# BuckBoost.net
KiCad netlist of a schematic drawn in Altium Designer
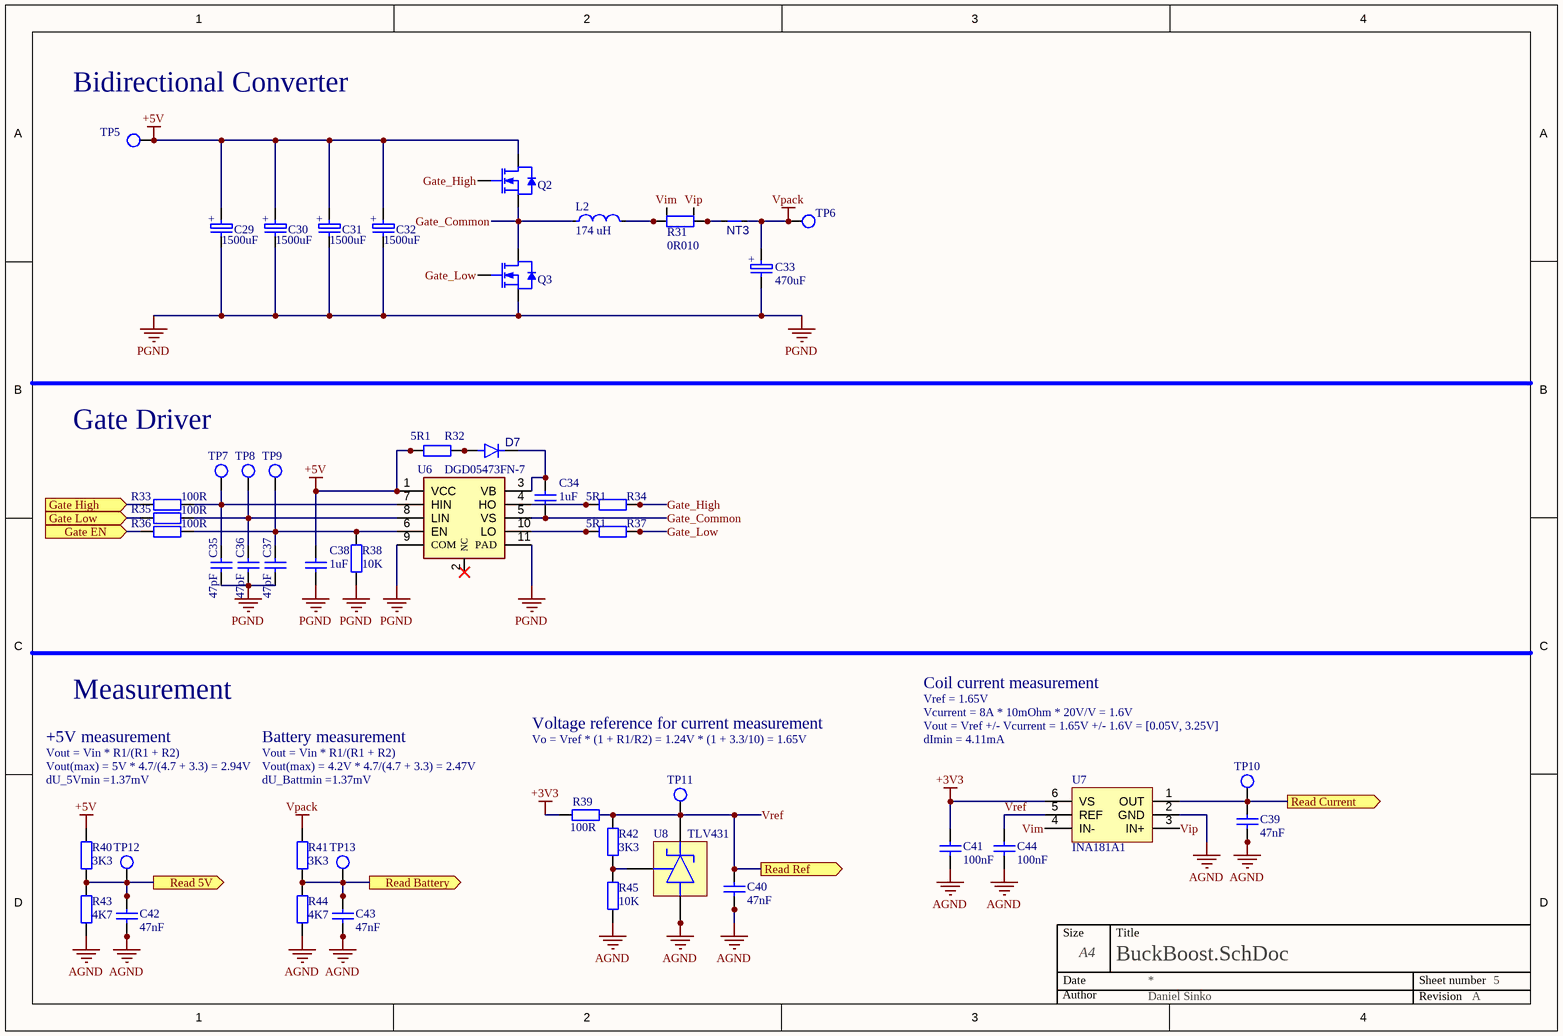
[diagram p0: BuckBoost.SchDoc]

(export (version "E")
  (design (tool "Eeschema 10.0.6"))
  (components
    (comp (ref "C29")
      (value "1500uF")
      (footprint "Aluminium Capacitor 10x12.5")
      (fields
        (field (name "MANUFACTURER") "Nichicon")
        (field (name "MANUFACTURER PART NUMBER") "RNU0J152MDN1PH")
      )
      (libsource (lib "UPS_Schlib") (part "1500uF"))
    )
    (comp (ref "C30")
      (value "1500uF")
      (footprint "Aluminium Capacitor 10x12.5")
      (fields
        (field (name "MANUFACTURER") "Nichicon")
        (field (name "MANUFACTURER PART NUMBER") "RNU0J152MDN1PH")
      )
      (libsource (lib "UPS_Schlib") (part "1500uF"))
    )
    (comp (ref "C31")
      (value "1500uF")
      (footprint "Aluminium Capacitor 10x12.5")
      (fields
        (field (name "MANUFACTURER") "Nichicon")
        (field (name "MANUFACTURER PART NUMBER") "RNU0J152MDN1PH")
      )
      (libsource (lib "UPS_Schlib") (part "1500uF"))
    )
    (comp (ref "C32")
      (value "1500uF")
      (footprint "Aluminium Capacitor 10x12.5")
      (fields
        (field (name "MANUFACTURER") "Nichicon")
        (field (name "MANUFACTURER PART NUMBER") "RNU0J152MDN1PH")
      )
      (libsource (lib "UPS_Schlib") (part "1500uF"))
    )
    (comp (ref "C33")
      (value "470uF")
      (footprint "Aluminium Capacitor 10x12.5")
      (description "Aluminum Electrolytic Capacitor, Aluminum (solid Polymer)")
      (fields
        (field (name "MANUFACTURER") "Nichicon")
        (field (name "MANUFACTURER PART NUMBER") "RR50J471MDN1KX")
      )
      (libsource (lib "UPS_Schlib") (part "RR50J471MDN1KX"))
    )
    (comp (ref "C34")
      (value "1uF")
      (footprint "CAP0603")
      (fields
        (field (name "MANUFACTURER") "Walsin Technologies")
        (field (name "MANUFACTURER PART NUMBER") "SH18B105K160CT")
      )
      (libsource (lib "UPS_Schlib") (part "1uF"))
    )
    (comp (ref "C35")
      (value "47pF")
      (footprint "CAP0603")
      (fields
        (field (name "MANUFACTURER") "KEMET")
        (field (name "MANUFACTURER PART NUMBER") "C0603C470J1GACTU")
      )
      (libsource (lib "UPS_Schlib") (part "47pF"))
    )
    (comp (ref "C36")
      (value "47pF")
      (footprint "CAP0603")
      (fields
        (field (name "MANUFACTURER") "KEMET")
        (field (name "MANUFACTURER PART NUMBER") "C0603C470J1GACTU")
      )
      (libsource (lib "UPS_Schlib") (part "47pF"))
    )
    (comp (ref "C37")
      (value "47pF")
      (footprint "CAP0603")
      (fields
        (field (name "MANUFACTURER") "KEMET")
        (field (name "MANUFACTURER PART NUMBER") "C0603C470J1GACTU")
      )
      (libsource (lib "UPS_Schlib") (part "47pF"))
    )
    (comp (ref "C38")
      (value "1uF")
      (footprint "CAP0603")
      (fields
        (field (name "MANUFACTURER") "Walsin Technologies")
        (field (name "MANUFACTURER PART NUMBER") "SH18B105K160CT")
      )
      (libsource (lib "UPS_Schlib") (part "1uF"))
    )
    (comp (ref "C39")
      (value "47nF")
      (footprint "CAP0603")
      (fields
        (field (name "MANUFACTURER") "Vishay Vitramon")
        (field (name "MANUFACTURER PART NUMBER") "VJ0603Y473KXJCW1BC")
      )
      (libsource (lib "UPS_Schlib") (part "47nF"))
    )
    (comp (ref "C40")
      (value "47nF")
      (footprint "CAP0603")
      (fields
        (field (name "MANUFACTURER") "Vishay Vitramon")
        (field (name "MANUFACTURER PART NUMBER") "VJ0603Y473KXJCW1BC")
      )
      (libsource (lib "UPS_Schlib") (part "47nF"))
    )
    (comp (ref "C41")
      (value "100nF")
      (footprint "CAP0603")
      (fields
        (field (name "MANUFACTURER") "Samsung")
        (field (name "MANUFACTURER PART NUMBER") "CL10B104KA8WPNC")
      )
      (libsource (lib "UPS_Schlib") (part "100nF"))
    )
    (comp (ref "C42")
      (value "47nF")
      (footprint "CAP0603")
      (fields
        (field (name "MANUFACTURER") "Vishay Vitramon")
        (field (name "MANUFACTURER PART NUMBER") "VJ0603Y473KXJCW1BC")
      )
      (libsource (lib "UPS_Schlib") (part "47nF"))
    )
    (comp (ref "C43")
      (value "47nF")
      (footprint "CAP0603")
      (fields
        (field (name "MANUFACTURER") "Vishay Vitramon")
        (field (name "MANUFACTURER PART NUMBER") "VJ0603Y473KXJCW1BC")
      )
      (libsource (lib "UPS_Schlib") (part "47nF"))
    )
    (comp (ref "C44")
      (value "100nF")
      (footprint "CAP0603")
      (fields
        (field (name "MANUFACTURER") "Samsung")
        (field (name "MANUFACTURER PART NUMBER") "CL10B104KA8WPNC")
      )
      (libsource (lib "UPS_Schlib") (part "100nF"))
    )
    (comp (ref "D7")
      (value "VS-MBRS130L-M3/5BT")
      (footprint "SMB")
      (description "Rectifier Diode, Schottky, 1 Phase, 1 Element, 30V V(RRM), Silicon")
      (fields (field (name "MANUFACTURER") "Vishay Semiconductors"))
      (libsource (lib "UPS_Schlib") (part "VS-MBRS130L-M3/5BT"))
    )
    (comp (ref "L2")
      (value "174 uH")
      (footprint "COIL_HANDMADE")
      (description "Hand made inductance")
      (fields (field (name "Comment") "Inductor"))
      (libsource (lib "UPS_Schlib") (part "Inductor"))
    )
    (comp (ref "NT3")
      (value "NetTie_1-1")
      (footprint "NETTIE_1.85MM")
      (description "NetTie 1 -> 1")
      (libsource (lib "UPS_Schlib") (part "NetTie_1-1"))
    )
    (comp (ref "Q2")
      (value "N-MOSFET")
      (footprint "SOT-669-5")
      (fields
        (field (name "MANUFACTURER") "Nexperia")
        (field (name "MANUFACTURER PART NUMBER") "PSMN1R2-25YLDX")
      )
      (libsource (lib "UPS_Schlib") (part "PSMN1R2-25YLDX"))
    )
    (comp (ref "Q3")
      (value "N-MOSFET")
      (footprint "SOT-669-5")
      (fields
        (field (name "MANUFACTURER") "Nexperia")
        (field (name "MANUFACTURER PART NUMBER") "PSMN1R2-25YLDX")
      )
      (libsource (lib "UPS_Schlib") (part "PSMN1R2-25YLDX"))
    )
    (comp (ref "R31")
      (value "0R010")
      (footprint "RES1206_KELVIN")
      (description "Resistor Current Sense Metal Foil 1206 10m Ohm 1% 1W ±50ppm/°C T/R")
      (fields
        (field (name "MANUFACTURER") "Eaton")
        (field (name "MANUFACTURER PART NUMBER") "MFSA1206R0050FCM")
      )
      (libsource (lib "UPS_Schlib") (part "0R010"))
    )
    (comp (ref "R32")
      (value "5R1")
      (footprint "RES0603")
      (description "Fixed Resistor, Thin Film, 0.1W, 5.1ohm, 75V, 0.5% +/-Tol, 25ppm/Cel, Surface Mount, 0603")
      (fields
        (field (name "MANUFACTURER") "Yageo")
        (field (name "MANUFACTURER PART NUMBER") "RT0603DRD075R1L")
      )
      (libsource (lib "UPS_Schlib") (part "5R"))
    )
    (comp (ref "R33")
      (value "100R")
      (footprint "RES0603")
      (fields
        (field (name "MANUFACTURER") "Yageo")
        (field (name "MANUFACTURER PART NUMBER") "RC0603JR-13100RL")
      )
      (libsource (lib "UPS_Schlib") (part "100R"))
    )
    (comp (ref "R34")
      (value "5R1")
      (footprint "RES0603")
      (description "Fixed Resistor, Thin Film, 0.1W, 5.1ohm, 75V, 0.5% +/-Tol, 25ppm/Cel, Surface Mount, 0603")
      (fields
        (field (name "MANUFACTURER") "Yageo")
        (field (name "MANUFACTURER PART NUMBER") "RT0603DRD075R1L")
      )
      (libsource (lib "UPS_Schlib") (part "5R"))
    )
    (comp (ref "R35")
      (value "100R")
      (footprint "RES0603")
      (fields
        (field (name "MANUFACTURER") "Yageo")
        (field (name "MANUFACTURER PART NUMBER") "RC0603JR-13100RL")
      )
      (libsource (lib "UPS_Schlib") (part "100R"))
    )
    (comp (ref "R36")
      (value "100R")
      (footprint "RES0603")
      (fields
        (field (name "MANUFACTURER") "Yageo")
        (field (name "MANUFACTURER PART NUMBER") "RC0603JR-13100RL")
      )
      (libsource (lib "UPS_Schlib") (part "100R"))
    )
    (comp (ref "R37")
      (value "5R1")
      (footprint "RES0603")
      (description "Fixed Resistor, Thin Film, 0.1W, 5.1ohm, 75V, 0.5% +/-Tol, 25ppm/Cel, Surface Mount, 0603")
      (fields
        (field (name "MANUFACTURER") "Yageo")
        (field (name "MANUFACTURER PART NUMBER") "RT0603DRD075R1L")
      )
      (libsource (lib "UPS_Schlib") (part "5R"))
    )
    (comp (ref "R38")
      (value "10K")
      (footprint "RES0603")
      (fields
        (field (name "MANUFACTURER") "Bourns")
        (field (name "MANUFACTURER PART NUMBER") "CR0603-FX-1002ELF")
      )
      (libsource (lib "") (part "10K_1"))
    )
    (comp (ref "R39")
      (value "100R")
      (footprint "RES0603")
      (fields
        (field (name "MANUFACTURER") "Yageo")
        (field (name "MANUFACTURER PART NUMBER") "RC0603JR-13100RL")
      )
      (libsource (lib "UPS_Schlib") (part "100R"))
    )
    (comp (ref "R40")
      (value "3K3")
      (footprint "RES0603")
      (fields
        (field (name "TOLERANCE") "1%")
        (field (name "POWER") "100mW")
        (field (name "MANUFACTURER") "Yageo")
      )
      (libsource (lib "UPS_Schlib") (part "3K3"))
    )
    (comp (ref "R41")
      (value "3K3")
      (footprint "RES0603")
      (fields
        (field (name "TOLERANCE") "1%")
        (field (name "POWER") "100mW")
        (field (name "MANUFACTURER") "Yageo")
      )
      (libsource (lib "UPS_Schlib") (part "3K3"))
    )
    (comp (ref "R42")
      (value "3K3")
      (footprint "RES0603")
      (fields
        (field (name "TOLERANCE") "1%")
        (field (name "POWER") "100mW")
        (field (name "MANUFACTURER") "Yageo")
      )
      (libsource (lib "UPS_Schlib") (part "3K3"))
    )
    (comp (ref "R43")
      (value "4K7")
      (footprint "RES0603")
      (fields
        (field (name "MANUFACTURER") "Yageo")
        (field (name "MANUFACTURER PART NUMBER") "AC0603FR-134K7L")
      )
      (libsource (lib "UPS_Schlib") (part "4K7"))
    )
    (comp (ref "R44")
      (value "4K7")
      (footprint "RES0603")
      (fields
        (field (name "MANUFACTURER") "Yageo")
        (field (name "MANUFACTURER PART NUMBER") "AC0603FR-134K7L")
      )
      (libsource (lib "UPS_Schlib") (part "4K7"))
    )
    (comp (ref "R45")
      (value "10K")
      (footprint "RES0603")
      (fields
        (field (name "MANUFACTURER") "Bourns")
        (field (name "MANUFACTURER PART NUMBER") "CR0603-FX-1002ELF")
      )
      (libsource (lib "UPS_Schlib") (part "10K"))
    )
    (comp (ref "TP5")
      (value "Test Point")
      (footprint "TP-1.5HOLE")
      (libsource (lib "UPS_Schlib") (part "Test Point"))
    )
    (comp (ref "TP6")
      (value "Test Point")
      (footprint "TP-1.5HOLE")
      (libsource (lib "UPS_Schlib") (part "Test Point"))
    )
    (comp (ref "TP7")
      (value "Test Point")
      (footprint "TP-1.5HOLE")
      (libsource (lib "UPS_Schlib") (part "Test Point"))
    )
    (comp (ref "TP8")
      (value "Test Point")
      (footprint "TP-1.5HOLE")
      (libsource (lib "UPS_Schlib") (part "Test Point"))
    )
    (comp (ref "TP9")
      (value "Test Point")
      (footprint "TP-1.5HOLE")
      (libsource (lib "UPS_Schlib") (part "Test Point"))
    )
    (comp (ref "TP10")
      (value "Test Point")
      (footprint "TP-1.5HOLE")
      (libsource (lib "UPS_Schlib") (part "Test Point"))
    )
    (comp (ref "TP11")
      (value "Test Point")
      (footprint "TP-1.5HOLE")
      (libsource (lib "UPS_Schlib") (part "Test Point"))
    )
    (comp (ref "TP12")
      (value "Test Point")
      (footprint "TP-1.5HOLE")
      (libsource (lib "UPS_Schlib") (part "Test Point"))
    )
    (comp (ref "TP13")
      (value "Test Point")
      (footprint "TP-1.5HOLE")
      (libsource (lib "UPS_Schlib") (part "Test Point"))
    )
    (comp (ref "U6")
      (value "DGD05473FN-7")
      (footprint "V-DFN3030-10")
      (description "Half Bridge Based MOSFET Driver")
      (fields (field (name "MANUFACTURER") "Diodes"))
      (libsource (lib "UPS_Schlib") (part "DGD05473FN-7"))
    )
    (comp (ref "U7")
      (value "INA181A1")
      (footprint "SOT23-6")
      (description "Operational Amplifier, 1 Func, 500uV Offset-Max, PDSO6")
      (fields
        (field (name "MANUFACTURER") "Texas Instruments")
        (field (name "MANUFACTURER PART NUMBER") "INA181A1IDBVR")
      )
      (libsource (lib "UPS_Schlib") (part "INA181A1"))
    )
    (comp (ref "U8")
      (value "TLV431")
      (footprint "SOT23-5")
      (description "Three Terminal Voltage Reference, 1 Output, 1.24V, Trim/Adjustable, BIPolar, PDSO5")
      (fields
        (field (name "MANUFACTURER") "Texas Instruments")
        (field (name "MANUFACTURER PART NUMBER") "TLV431CDBVR")
      )
      (libsource (lib "UPS_Schlib") (part "TLV431"))
    )
  )
  (nets
    (net (code "1") (name "+3V3") (class "Default")
      (node (ref "C41") (pin "1") (pinfunction "1_1") (pintype "passive"))
      (node (ref "R39") (pin "1") (pinfunction "1_1") (pintype "passive"))
      (node (ref "U7") (pin "6") (pinfunction "VS_6") (pintype "power_in"))
    )
    (net (code "2") (name "+5V") (class "Default")
      (node (ref "C29") (pin "2") (pinfunction "A_2") (pintype "passive"))
      (node (ref "C30") (pin "2") (pinfunction "A_2") (pintype "passive"))
      (node (ref "C31") (pin "2") (pinfunction "A_2") (pintype "passive"))
      (node (ref "C32") (pin "2") (pinfunction "A_2") (pintype "passive"))
      (node (ref "C38") (pin "2") (pinfunction "2_2") (pintype "passive"))
      (node (ref "Q2") (pin "3") (pinfunction "D_3") (pintype "passive"))
      (node (ref "R32") (pin "1") (pinfunction "1_1") (pintype "passive"))
      (node (ref "R40") (pin "2") (pinfunction "2_2") (pintype "passive"))
      (node (ref "TP5") (pin "1") (pintype "passive"))
      (node (ref "U6") (pin "1") (pinfunction "VCC_1") (pintype "passive"))
    )
    (net (code "3") (name "/Gate EN") (class "Default")
      (node (ref "R36") (pin "1") (pinfunction "1_1") (pintype "passive"))
    )
    (net (code "4") (name "/Gate High") (class "Default")
      (node (ref "R33") (pin "1") (pinfunction "1_1") (pintype "passive"))
    )
    (net (code "5") (name "/Gate Low") (class "Default")
      (node (ref "R35") (pin "1") (pinfunction "1_1") (pintype "passive"))
    )
    (net (code "6") (name "/Gate_Common") (class "Default")
      (node (ref "C34") (pin "1") (pinfunction "1_1") (pintype "passive"))
      (node (ref "L2") (pin "1") (pinfunction "1_1") (pintype "passive"))
      (node (ref "Q2") (pin "2") (pinfunction "S_2") (pintype "passive"))
      (node (ref "Q3") (pin "3") (pinfunction "D_3") (pintype "passive"))
      (node (ref "U6") (pin "5") (pinfunction "VS_5") (pintype "passive"))
    )
    (net (code "7") (name "/Gate_High") (class "Default")
      (node (ref "Q2") (pin "1") (pinfunction "G_1") (pintype "passive"))
      (node (ref "R34") (pin "2") (pinfunction "2_2") (pintype "passive"))
    )
    (net (code "8") (name "/Gate_Low") (class "Default")
      (node (ref "Q3") (pin "1") (pinfunction "G_1") (pintype "passive"))
      (node (ref "R37") (pin "2") (pinfunction "2_2") (pintype "passive"))
    )
    (net (code "9") (name "/Read 5V") (class "Default")
      (node (ref "C42") (pin "2") (pinfunction "2_2") (pintype "passive"))
      (node (ref "R40") (pin "1") (pinfunction "1_1") (pintype "passive"))
      (node (ref "R43") (pin "2") (pinfunction "2_2") (pintype "passive"))
      (node (ref "TP12") (pin "1") (pintype "passive"))
    )
    (net (code "10") (name "/Read Battery") (class "Default")
      (node (ref "C43") (pin "2") (pinfunction "2_2") (pintype "passive"))
      (node (ref "R41") (pin "1") (pinfunction "1_1") (pintype "passive"))
      (node (ref "R44") (pin "2") (pinfunction "2_2") (pintype "passive"))
      (node (ref "TP13") (pin "1") (pintype "passive"))
    )
    (net (code "11") (name "/Read Current") (class "Default")
      (node (ref "C39") (pin "2") (pinfunction "2_2") (pintype "passive"))
      (node (ref "TP10") (pin "1") (pintype "passive"))
      (node (ref "U7") (pin "1") (pinfunction "OUT_1") (pintype "passive"))
    )
    (net (code "12") (name "/Vim") (class "Default")
      (node (ref "R31") (pin "3") (pinfunction "3_3") (pintype "passive"))
      (node (ref "U7") (pin "4") (pinfunction "IN-_4") (pintype "passive"))
    )
    (net (code "13") (name "/Vip") (class "Default")
      (node (ref "R31") (pin "4") (pinfunction "4_4") (pintype "passive"))
      (node (ref "U7") (pin "3") (pinfunction "IN+_3") (pintype "passive"))
    )
    (net (code "14") (name "/Vref") (class "Default")
      (node (ref "C40") (pin "2") (pinfunction "2_2") (pintype "passive"))
      (node (ref "C44") (pin "1") (pinfunction "1_1") (pintype "passive"))
      (node (ref "R39") (pin "2") (pinfunction "2_2") (pintype "passive"))
      (node (ref "R42") (pin "2") (pinfunction "2_2") (pintype "passive"))
      (node (ref "TP11") (pin "1") (pintype "passive"))
      (node (ref "U7") (pin "5") (pinfunction "REF_5") (pintype "passive"))
      (node (ref "U8") (pin "3") (pinfunction "K_3") (pintype "passive"))
    )
    (net (code "15") (name "AGND") (class "Default")
      (node (ref "C39") (pin "1") (pinfunction "1_1") (pintype "passive"))
      (node (ref "C40") (pin "1") (pinfunction "1_1") (pintype "passive"))
      (node (ref "C41") (pin "2") (pinfunction "2_2") (pintype "passive"))
      (node (ref "C42") (pin "1") (pinfunction "1_1") (pintype "passive"))
      (node (ref "C43") (pin "1") (pinfunction "1_1") (pintype "passive"))
      (node (ref "C44") (pin "2") (pinfunction "2_2") (pintype "passive"))
      (node (ref "R43") (pin "1") (pinfunction "1_1") (pintype "passive"))
      (node (ref "R44") (pin "1") (pinfunction "1_1") (pintype "passive"))
      (node (ref "R45") (pin "1") (pinfunction "1_1") (pintype "passive"))
      (node (ref "U7") (pin "2") (pinfunction "GND_2") (pintype "passive"))
      (node (ref "U8") (pin "2") (pinfunction "*_2") (pintype "passive"))
      (node (ref "U8") (pin "5") (pinfunction "A_5") (pintype "passive"))
    )
    (net (code "16") (name "Net-(D7-A)") (class "Default")
      (node (ref "D7") (pin "2") (pinfunction "A_2") (pintype "passive"))
      (node (ref "R32") (pin "2") (pinfunction "2_2") (pintype "passive"))
    )
    (net (code "17") (name "Net-(D7-K)") (class "Default")
      (node (ref "C34") (pin "2") (pinfunction "2_2") (pintype "passive"))
      (node (ref "D7") (pin "1") (pinfunction "K_1") (pintype "passive"))
      (node (ref "U6") (pin "3") (pinfunction "VB_3") (pintype "passive"))
    )
    (net (code "18") (name "Net-(L2-Pad2)") (class "Default")
      (node (ref "L2") (pin "2") (pinfunction "2_2") (pintype "passive"))
      (node (ref "R31") (pin "1") (pinfunction "1_1") (pintype "passive"))
    )
    (net (code "19") (name "Net-(NT3-Pad1)") (class "Default")
      (node (ref "NT3") (pin "1") (pinfunction "1_1") (pintype "passive"))
      (node (ref "R31") (pin "2") (pinfunction "2_2") (pintype "passive"))
    )
    (net (code "20") (name "Net-(U6-EN)") (class "Default")
      (node (ref "C37") (pin "2") (pinfunction "2_2") (pintype "passive"))
      (node (ref "R36") (pin "2") (pinfunction "2_2") (pintype "passive"))
      (node (ref "R38") (pin "1") (pinfunction "1_1") (pintype "passive"))
      (node (ref "TP9") (pin "1") (pintype "passive"))
      (node (ref "U6") (pin "6") (pinfunction "EN_6") (pintype "passive"))
    )
    (net (code "21") (name "Net-(U6-HIN)") (class "Default")
      (node (ref "C35") (pin "2") (pinfunction "2_2") (pintype "passive"))
      (node (ref "R33") (pin "2") (pinfunction "2_2") (pintype "passive"))
      (node (ref "TP7") (pin "1") (pintype "passive"))
      (node (ref "U6") (pin "7") (pinfunction "HIN_7") (pintype "passive"))
    )
    (net (code "22") (name "Net-(U6-HO)") (class "Default")
      (node (ref "R34") (pin "1") (pinfunction "1_1") (pintype "passive"))
      (node (ref "U6") (pin "4") (pinfunction "HO_4") (pintype "passive"))
    )
    (net (code "23") (name "Net-(U6-LIN)") (class "Default")
      (node (ref "C36") (pin "2") (pinfunction "2_2") (pintype "passive"))
      (node (ref "R35") (pin "2") (pinfunction "2_2") (pintype "passive"))
      (node (ref "TP8") (pin "1") (pintype "passive"))
      (node (ref "U6") (pin "8") (pinfunction "LIN_8") (pintype "passive"))
    )
    (net (code "24") (name "Net-(U6-LO)") (class "Default")
      (node (ref "R37") (pin "1") (pinfunction "1_1") (pintype "passive"))
      (node (ref "U6") (pin "10") (pinfunction "LO_10") (pintype "passive"))
    )
    (net (code "25") (name "Net-(U8-REF)") (class "Default")
      (node (ref "R42") (pin "1") (pinfunction "1_1") (pintype "passive"))
      (node (ref "R45") (pin "2") (pinfunction "2_2") (pintype "passive"))
      (node (ref "U8") (pin "4") (pinfunction "REF_4") (pintype "passive"))
    )
    (net (code "26") (name "PGND") (class "Default")
      (node (ref "C29") (pin "1") (pinfunction "C_1") (pintype "passive"))
      (node (ref "C30") (pin "1") (pinfunction "C_1") (pintype "passive"))
      (node (ref "C31") (pin "1") (pinfunction "C_1") (pintype "passive"))
      (node (ref "C32") (pin "1") (pinfunction "C_1") (pintype "passive"))
      (node (ref "C33") (pin "1") (pinfunction "C_1") (pintype "passive"))
      (node (ref "C35") (pin "1") (pinfunction "1_1") (pintype "passive"))
      (node (ref "C36") (pin "1") (pinfunction "1_1") (pintype "passive"))
      (node (ref "C37") (pin "1") (pinfunction "1_1") (pintype "passive"))
      (node (ref "C38") (pin "1") (pinfunction "1_1") (pintype "passive"))
      (node (ref "Q3") (pin "2") (pinfunction "S_2") (pintype "passive"))
      (node (ref "R38") (pin "2") (pinfunction "2_2") (pintype "passive"))
      (node (ref "U6") (pin "11") (pinfunction "PAD_11") (pintype "passive"))
      (node (ref "U6") (pin "9") (pinfunction "COM_9") (pintype "passive"))
    )
    (net (code "27") (name "Vpack") (class "Default")
      (node (ref "C33") (pin "2") (pinfunction "A_2") (pintype "passive"))
      (node (ref "NT3") (pin "2") (pinfunction "2_2") (pintype "passive"))
      (node (ref "R41") (pin "2") (pinfunction "2_2") (pintype "passive"))
      (node (ref "TP6") (pin "1") (pintype "passive"))
    )
    (net (code "28") (name "unconnected-(U6-NC-Pad2)") (class "Default")
      (node (ref "U6") (pin "2") (pinfunction "NC_2") (pintype "passive+no_connect"))
    )
  )
)
